# ShieldV1_2b.net
KiCad netlist of a schematic drawn in EasyEDA
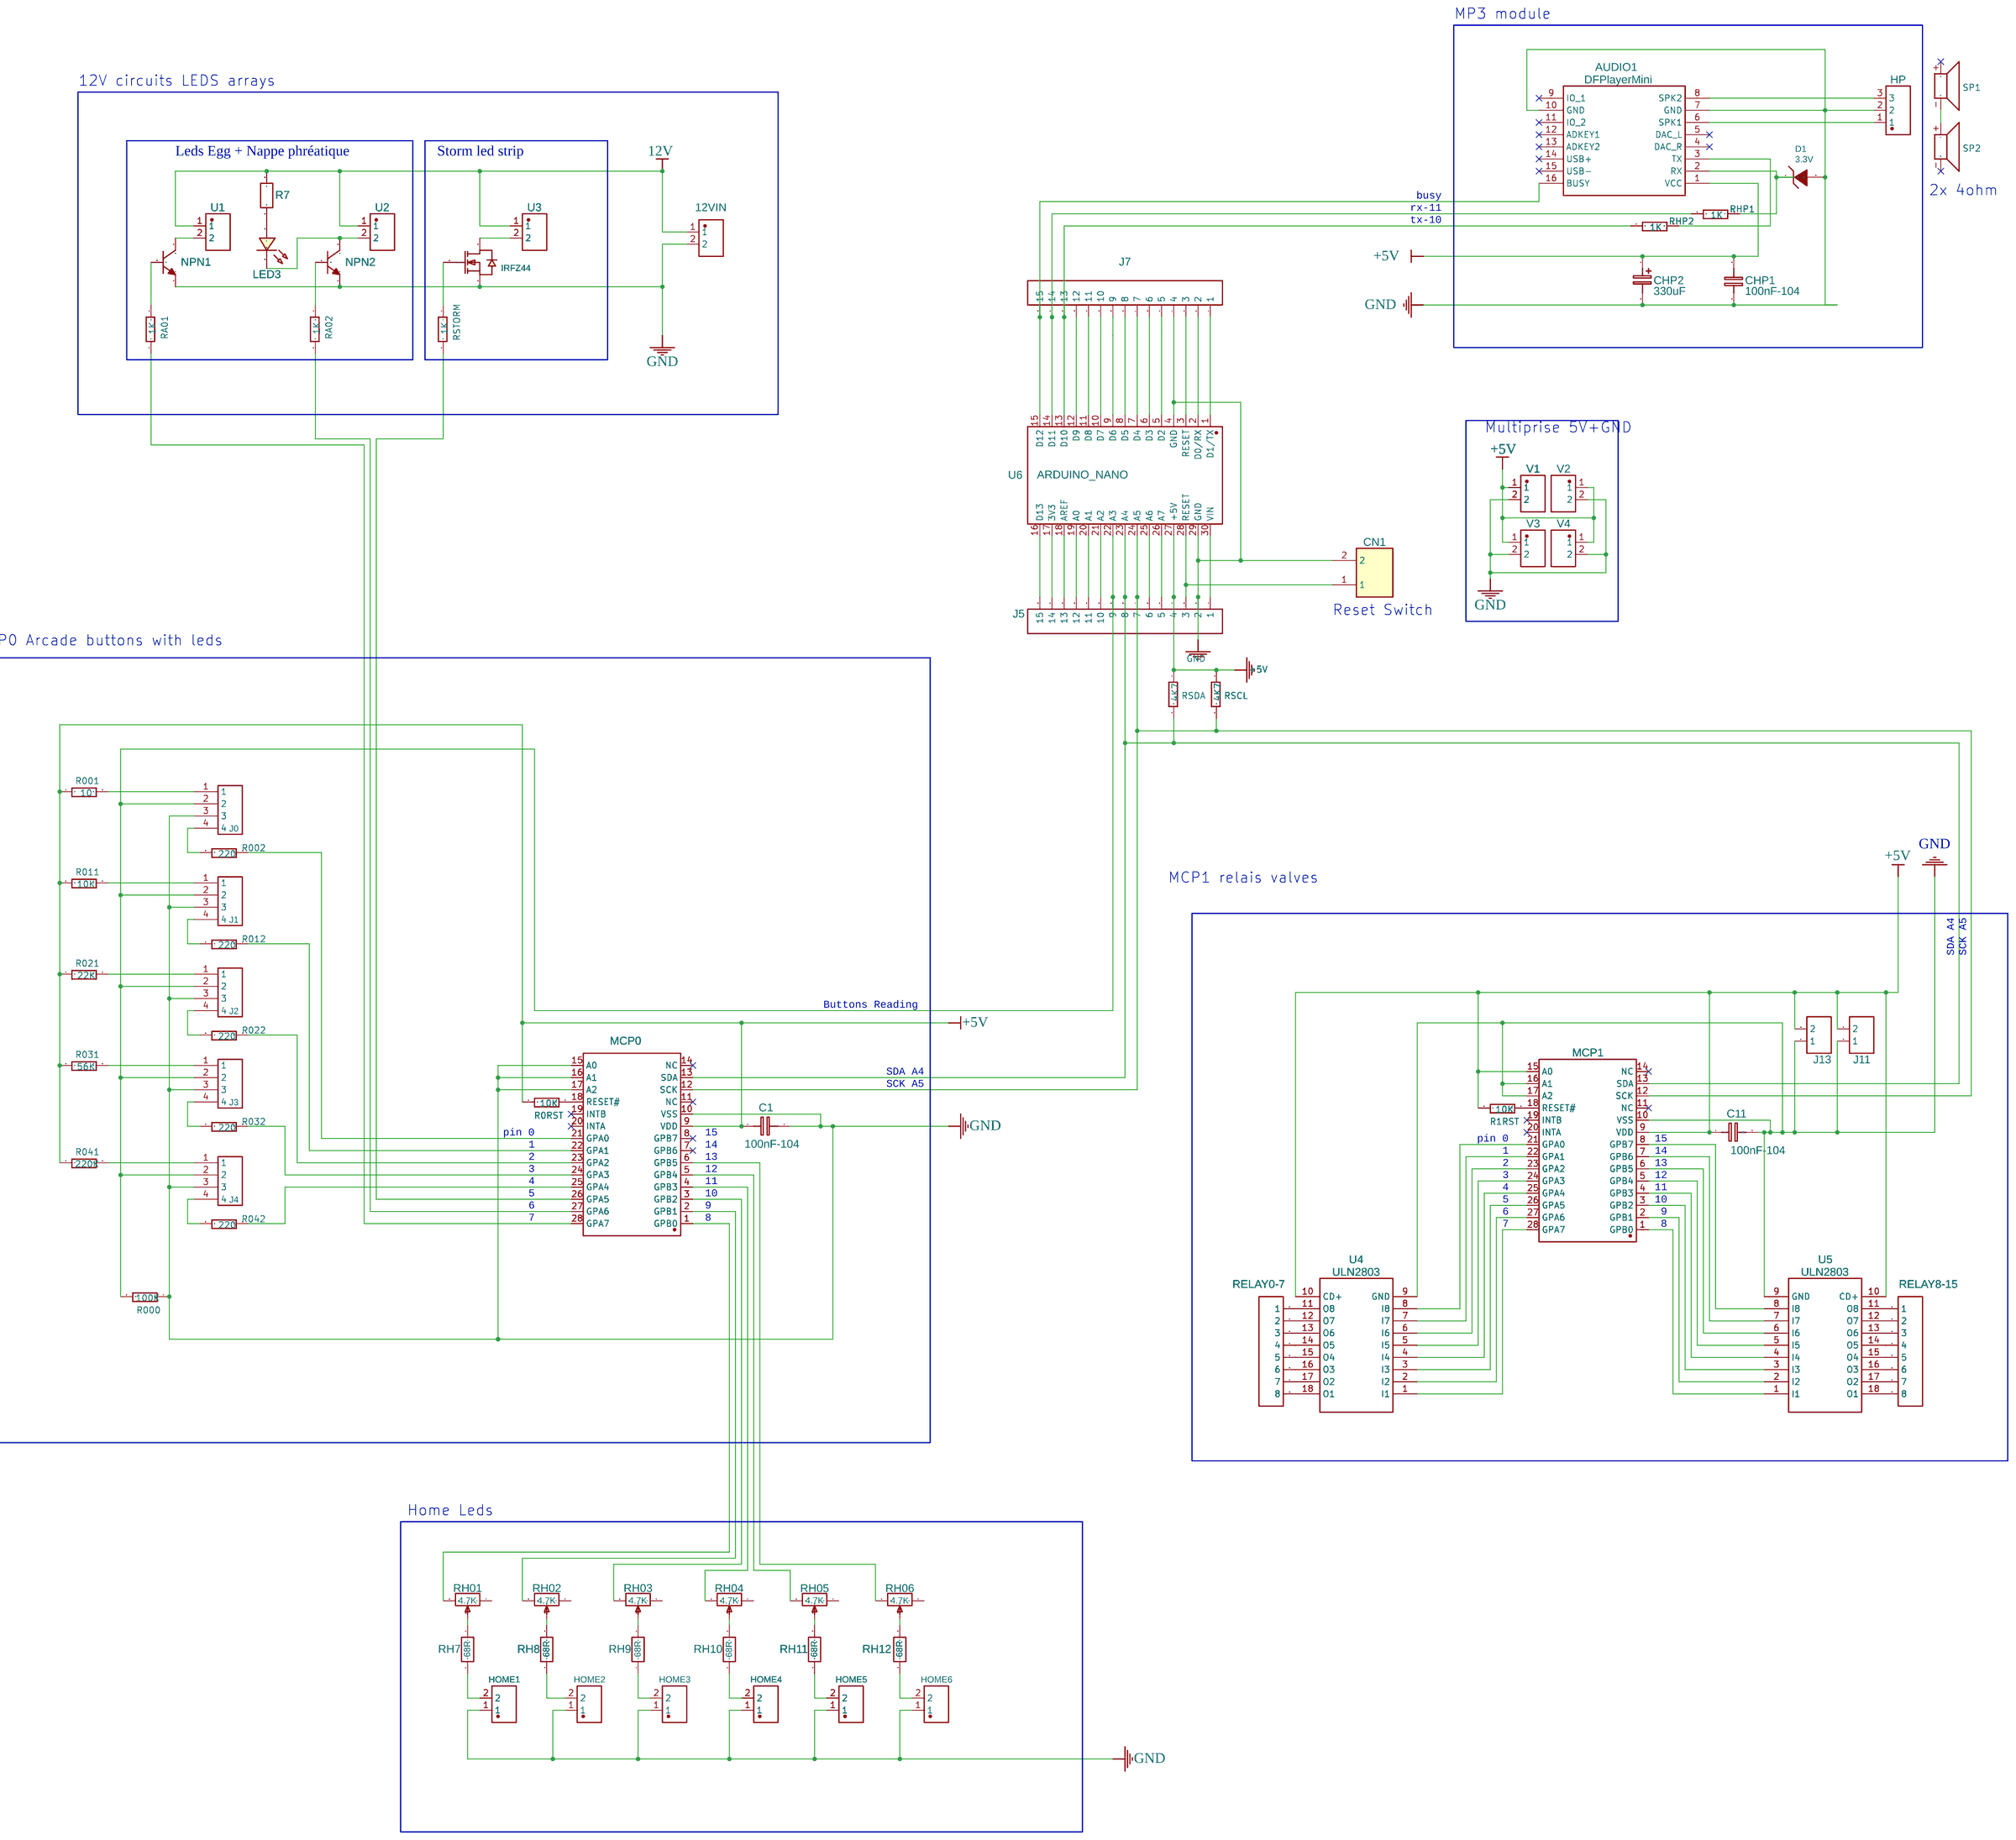
[diagram p0: Main board]
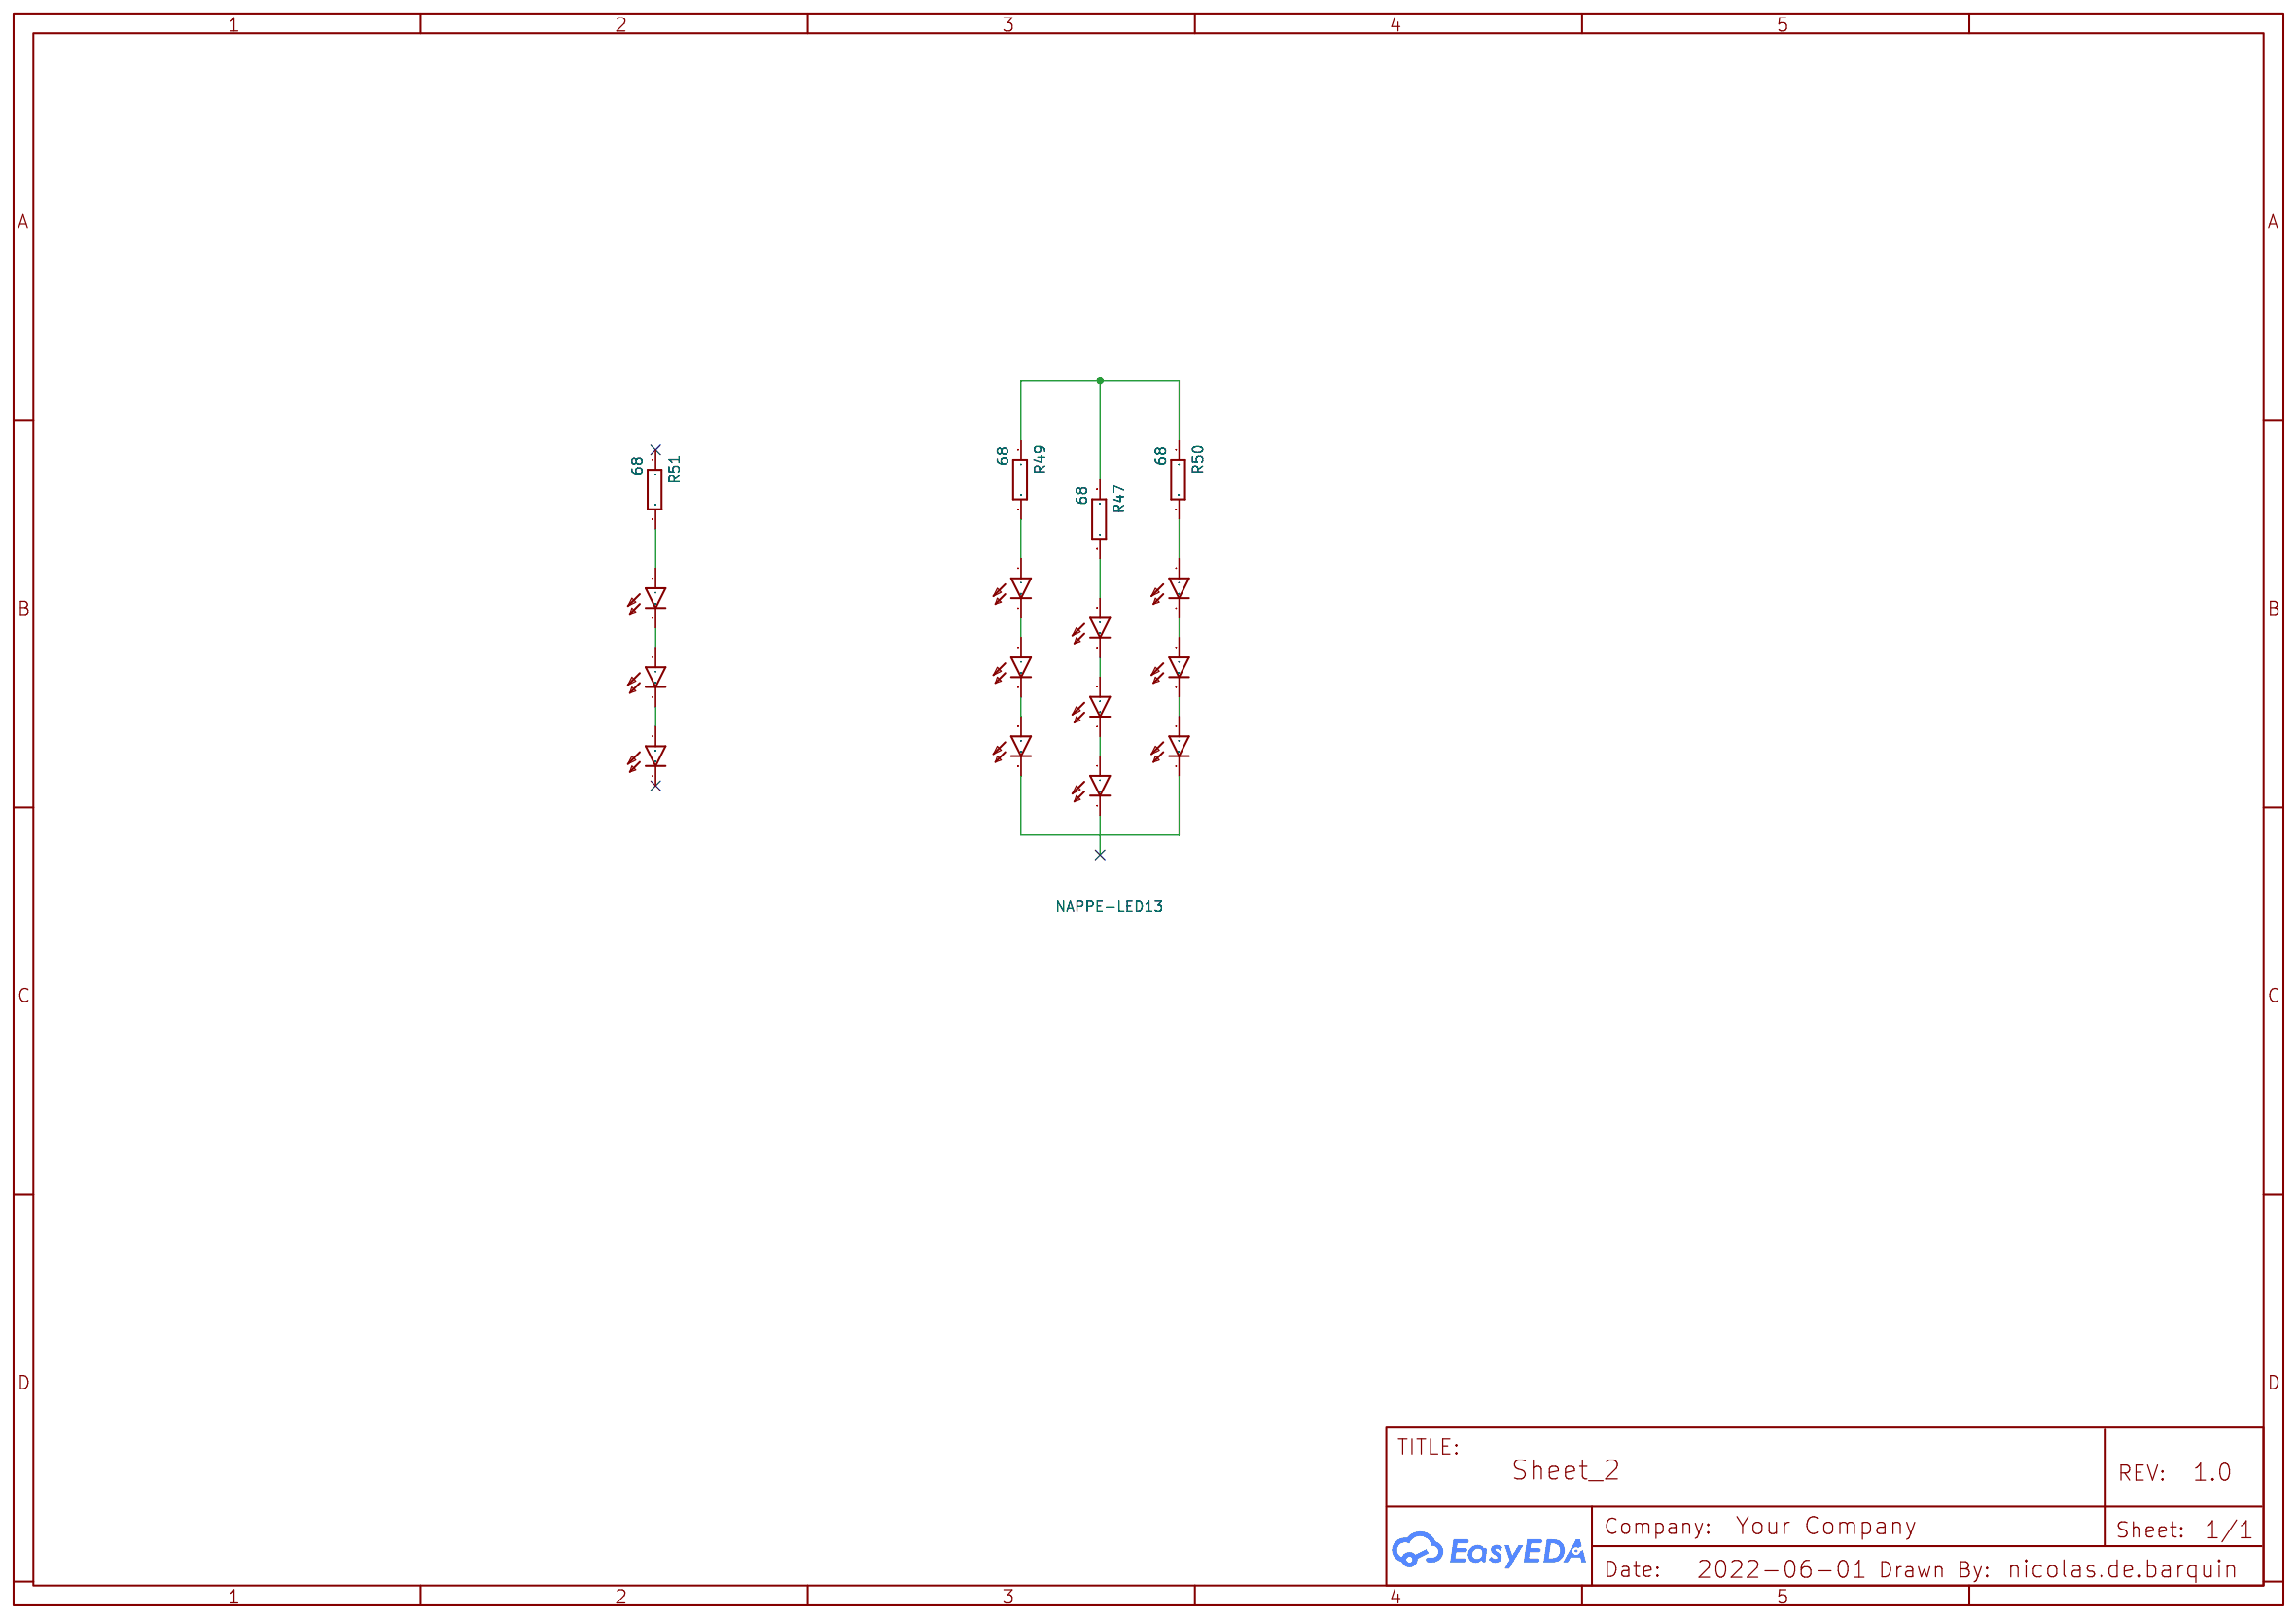
[diagram p1: leds]

(export (version "E")
  (design (tool "Eeschema 10.0.6"))
  (components
    (comp (ref "12VIN")
      (value "12V IN")
      (fields
        (field (name "BOM_Manufacturer Part") "KF301-5.0-2P")
        (field (name "BOM_Supplier Part") "C474881")
      )
      (libsource (lib "") (part "KF301-5.0-2P_1"))
    )
    (comp (ref "AUDIO1")
      (value "DFPlayerMini")
      (fields (field (name "BOM_Manufacturer Part") "DFPlayer mini"))
      (libsource (lib "") (part "DFPlayerMini"))
    )
    (comp (ref "C1") (value "100nF-104") (libsource (lib "") (part "C_RAD-0.1_EU_2")))
    (comp (ref "C11") (value "100nF-104") (libsource (lib "") (part "C_RAD-0.1_EU_1")))
    (comp (ref "CHP1") (value "100nF-104") (libsource (lib "") (part "C_RAD-0.1_EU")))
    (comp (ref "CHP2") (value "330uF") (libsource (lib "") (part "CE_TH_D6.3×F2.5_EU")))
    (comp (ref "CN1")
      (value "B2B-PH-K-S(LF)(SN)")
      (fields (field (name "BOM_Supplier Part") "C131337"))
      (libsource (lib "") (part "B2B-PH-K-S(LF)(SN)"))
    )
    (comp (ref "D1")
      (value "3.3V")
      (fields (field (name "BOM_Manufacturer Part") "1N5921BG") (field (name "BOM_Supplier Part") "C232466"))
      (libsource (lib "") (part "1N5921BG"))
    )
    (comp (ref "HOME1")
      (value "B2B-PH-KL")
      (fields (field (name "BOM_Supplier Part") "C2683610"))
      (libsource (lib "") (part "B2B-PH-KL"))
    )
    (comp (ref "HOME2")
      (value "B2B-PH-KL")
      (fields (field (name "BOM_Supplier Part") "C2683610"))
      (libsource (lib "") (part "B2B-PH-KL"))
    )
    (comp (ref "HOME3")
      (value "B2B-PH-KL")
      (fields (field (name "BOM_Supplier Part") "C2683610"))
      (libsource (lib "") (part "B2B-PH-KL"))
    )
    (comp (ref "HOME4")
      (value "B2B-PH-KL")
      (fields (field (name "BOM_Supplier Part") "C2683610"))
      (libsource (lib "") (part "B2B-PH-KL"))
    )
    (comp (ref "HOME5")
      (value "B2B-PH-KL")
      (fields (field (name "BOM_Supplier Part") "C2683610"))
      (libsource (lib "") (part "B2B-PH-KL"))
    )
    (comp (ref "HOME6")
      (value "B2B-PH-KL")
      (fields (field (name "BOM_Supplier Part") "C2683610"))
      (libsource (lib "") (part "B2B-PH-KL"))
    )
    (comp (ref "HP")
      (value "JL300-50003U01")
      (fields (field (name "BOM_Supplier Part") "C394552"))
      (libsource (lib "") (part "JL300-50003U01"))
    )
    (comp (ref "IRFZ44")
      (value "IRFZ44NPBF")
      (fields (field (name "BOM_Supplier Part") "C2586"))
      (libsource (lib "") (part "IRFZ44NPBF"))
    )
    (comp (ref "J0")
      (value "XHB-4A(White)/4needle")
      (fields (field (name "BOM_Supplier Part") "C61277"))
      (libsource (lib "") (part "XHB-4A(White)/4needle"))
    )
    (comp (ref "J1")
      (value "XHB-4A(White)/4needle")
      (fields (field (name "BOM_Supplier Part") "C61277"))
      (libsource (lib "") (part "XHB-4A(White)/4needle"))
    )
    (comp (ref "J2")
      (value "XHB-4A(White)/4needle")
      (fields (field (name "BOM_Supplier Part") "C61277"))
      (libsource (lib "") (part "XHB-4A(White)/4needle"))
    )
    (comp (ref "J3")
      (value "XHB-4A(White)/4needle")
      (fields (field (name "BOM_Supplier Part") "C61277"))
      (libsource (lib "") (part "XHB-4A(White)/4needle"))
    )
    (comp (ref "J4")
      (value "XHB-4A(White)/4needle")
      (fields (field (name "BOM_Supplier Part") "C61277"))
      (libsource (lib "") (part "XHB-4A(White)/4needle"))
    )
    (comp (ref "J5")
      (value "HDR-M-2.54_1x15")
      (fields (field (name "BOM_Supplier Part") "C124373"))
      (libsource (lib "") (part "HDR-M-2.54_1x15"))
    )
    (comp (ref "J7")
      (value "HDR-M-2.54_1x15")
      (fields (field (name "BOM_Supplier Part") "C124373"))
      (libsource (lib "") (part "HDR-M-2.54_1x15_1"))
    )
    (comp (ref "J11")
      (value "HDR-M-2.54_1x2")
      (fields (field (name "BOM_Supplier Part") "C124375"))
      (libsource (lib "") (part "HDR-M-2.54_1x2"))
    )
    (comp (ref "J13")
      (value "HDR-M-2.54_1x2")
      (fields (field (name "BOM_Supplier Part") "C124375"))
      (libsource (lib "") (part "HDR-M-2.54_1x2"))
    )
    (comp (ref "LED3")
      (value "LED-0805_R")
      (fields
        (field (name "BOM_Manufacturer Part") "17-21SURC/S530-A3/TR8")
        (field (name "BOM_Supplier Part") "C72037")
      )
      (libsource (lib "") (part "LED-0805_R"))
    )
    (comp (ref "MCP0")
      (value "MCP23017-E/SP")
      (fields (field (name "BOM_Supplier Part") "C647352"))
      (libsource (lib "") (part "MCP23017-E/SP"))
    )
    (comp (ref "MCP1")
      (value "MCP23017-E/SP")
      (fields (field (name "BOM_Supplier Part") "C647352"))
      (libsource (lib "") (part "MCP23017-E/SP"))
    )
    (comp (ref "NPN1")
      (value "2N4401_C15986")
      (fields (field (name "BOM_Manufacturer Part") "2N4401") (field (name "BOM_Supplier Part") "C15986"))
      (libsource (lib "") (part "2N4401_C15986"))
    )
    (comp (ref "NPN2")
      (value "2N4401_C15986")
      (fields (field (name "BOM_Manufacturer Part") "2N4401") (field (name "BOM_Supplier Part") "C15986"))
      (libsource (lib "") (part "2N4401_C15986"))
    )
    (comp (ref "R000") (value "100K") (libsource (lib "") (part "Unknown_875_-695")))
    (comp (ref "R0RST") (value "10K") (libsource (lib "") (part "Unknown_1205_-855")))
    (comp (ref "R001") (value "10") (libsource (lib "") (part "Unknown_825_-1110")))
    (comp (ref "R1RST") (value "10K") (libsource (lib "") (part "Unknown_1990_-850")))
    (comp (ref "R002") (value "220") (libsource (lib "") (part "Unknown_940_-1060")))
    (comp (ref "R7") (value "1k") (libsource (lib "") (part "R_0805_EU")))
    (comp (ref "R011") (value "10K") (libsource (lib "") (part "Unknown_825_-1035")))
    (comp (ref "R012") (value "220") (libsource (lib "") (part "Unknown_940_-985")))
    (comp (ref "R021") (value "22K") (libsource (lib "") (part "Unknown_825_-960")))
    (comp (ref "R022") (value "220") (libsource (lib "") (part "Unknown_940_-910")))
    (comp (ref "R031") (value "56K") (libsource (lib "") (part "Unknown_825_-885")))
    (comp (ref "R032") (value "220") (libsource (lib "") (part "Unknown_940_-835")))
    (comp (ref "R041") (value "220K") (libsource (lib "") (part "Unknown_825_-805")))
    (comp (ref "R042") (value "220") (libsource (lib "") (part "Unknown_940_-755")))
    (comp (ref "RA01") (value "1K") (libsource (lib "") (part "Unknown_880_-1490")))
    (comp (ref "RA02") (value "1K") (libsource (lib "") (part "Unknown_1015_-1490")))
    (comp (ref "RELAY0-7")
      (value "HDR-M-2.54_1x8")
      (fields (field (name "BOM_Supplier Part") "C190820"))
      (libsource (lib "") (part "HDR-M-2.54_1x8_1"))
    )
    (comp (ref "RELAY8-15")
      (value "HDR-M-2.54_1x8")
      (fields (field (name "BOM_Supplier Part") "C190820"))
      (libsource (lib "") (part "HDR-M-2.54_1x8"))
    )
    (comp (ref "RH01")
      (value "4.7K")
      (fields
        (field (name "BOM_Manufacturer Part") "GF063P1-B101")
        (field (name "BOM_Supplier Part") "C128075")
      )
      (libsource (lib "") (part "GF063P1-B101"))
    )
    (comp (ref "RH02")
      (value "4.7K")
      (fields
        (field (name "BOM_Manufacturer Part") "GF063P1-B101")
        (field (name "BOM_Supplier Part") "C128075")
      )
      (libsource (lib "") (part "GF063P1-B101"))
    )
    (comp (ref "RH03")
      (value "4.7K")
      (fields
        (field (name "BOM_Manufacturer Part") "GF063P1-B101")
        (field (name "BOM_Supplier Part") "C128075")
      )
      (libsource (lib "") (part "GF063P1-B101"))
    )
    (comp (ref "RH04")
      (value "4.7K")
      (fields
        (field (name "BOM_Manufacturer Part") "GF063P1-B101")
        (field (name "BOM_Supplier Part") "C128075")
      )
      (libsource (lib "") (part "GF063P1-B101"))
    )
    (comp (ref "RH05")
      (value "4.7K")
      (fields
        (field (name "BOM_Manufacturer Part") "GF063P1-B101")
        (field (name "BOM_Supplier Part") "C128075")
      )
      (libsource (lib "") (part "GF063P1-B101"))
    )
    (comp (ref "RH06")
      (value "4.7K")
      (fields
        (field (name "BOM_Manufacturer Part") "GF063P1-B101")
        (field (name "BOM_Supplier Part") "C128075")
      )
      (libsource (lib "") (part "GF063P1-B101"))
    )
    (comp (ref "RH7") (value "68R") (libsource (lib "") (part "R_0805_EU_1")))
    (comp (ref "RH8") (value "68R") (libsource (lib "") (part "R_0805_EU_1")))
    (comp (ref "RH9") (value "68R") (libsource (lib "") (part "R_0805_EU_1")))
    (comp (ref "RH10") (value "68R") (libsource (lib "") (part "R_0805_EU_1")))
    (comp (ref "RH11") (value "68R") (libsource (lib "") (part "R_0805_EU_1")))
    (comp (ref "RH12") (value "68R") (libsource (lib "") (part "R_0805_EU_1")))
    (comp (ref "RHP1") (value "1K") (libsource (lib "") (part "Unknown_2165_-1585")))
    (comp (ref "RHP2") (value "1K") (libsource (lib "") (part "Unknown_2115_-1575")))
    (comp (ref "RSCL") (value "4K7") (libsource (lib "") (part "Unknown_1755_-1190")))
    (comp (ref "RSDA") (value "4K7") (libsource (lib "") (part "Unknown_1720_-1190")))
    (comp (ref "RSTORM") (value "1K") (libsource (lib "") (part "Unknown_1120_-1490")))
    (comp (ref "SP1") (value "SMS-1308MS-2-R") (libsource (lib "") (part "Unknown_2350_-1690")))
    (comp (ref "SP2") (value "SMS-1308MS-2-R") (libsource (lib "") (part "Unknown_2350_-1640")))
    (comp (ref "U1")
      (value "KF301-5.0-2P")
      (fields (field (name "BOM_Supplier Part") "C474881"))
      (libsource (lib "") (part "KF301-5.0-2P"))
    )
    (comp (ref "U2")
      (value "KF301-5.0-2P")
      (fields (field (name "BOM_Supplier Part") "C474881"))
      (libsource (lib "") (part "KF301-5.0-2P"))
    )
    (comp (ref "U3")
      (value "KF301-5.0-2P")
      (fields (field (name "BOM_Supplier Part") "C474881"))
      (libsource (lib "") (part "KF301-5.0-2P"))
    )
    (comp (ref "U4")
      (value "ULN2803")
      (fields
        (field (name "BOM_Manufacturer Part") "ULN2803G-D18-T")
        (field (name "BOM_Supplier Part") "C75528")
      )
      (libsource (lib "") (part "ULN2803G-D18-T_1"))
    )
    (comp (ref "U5")
      (value "ULN2803")
      (fields
        (field (name "BOM_Manufacturer Part") "ULN2803G-D18-T")
        (field (name "BOM_Supplier Part") "C75528")
      )
      (libsource (lib "") (part "ULN2803G-D18-T"))
    )
    (comp (ref "U6")
      (value "ARDUINO_NANO")
      (fields (field (name "BOM_Supplier Part") "C9900017879"))
      (libsource (lib "") (part "ARDUINO_NANO"))
    )
    (comp (ref "V1")
      (value "12V IN")
      (fields
        (field (name "BOM_Manufacturer Part") "KF301-5.0-2P")
        (field (name "BOM_Supplier Part") "C474881")
      )
      (libsource (lib "") (part "KF301-5.0-2P_2"))
    )
    (comp (ref "V2")
      (value "12V IN")
      (fields
        (field (name "BOM_Manufacturer Part") "KF301-5.0-2P")
        (field (name "BOM_Supplier Part") "C474881")
      )
      (libsource (lib "") (part "KF301-5.0-2P_3"))
    )
    (comp (ref "V3")
      (value "12V IN")
      (fields
        (field (name "BOM_Manufacturer Part") "KF301-5.0-2P")
        (field (name "BOM_Supplier Part") "C474881")
      )
      (libsource (lib "") (part "KF301-5.0-2P_2"))
    )
    (comp (ref "V4")
      (value "12V IN")
      (fields
        (field (name "BOM_Manufacturer Part") "KF301-5.0-2P")
        (field (name "BOM_Supplier Part") "C474881")
      )
      (libsource (lib "") (part "KF301-5.0-2P_3"))
    )
    (comp (ref "NAPPE-LED1") (value "LED5MM") (libsource (lib "") (part "Unknown_550_-460")))
    (comp (ref "NAPPE-LED2") (value "LED5MM") (libsource (lib "") (part "Unknown_550_-500")))
    (comp (ref "NAPPE-LED3") (value "LED5MM") (libsource (lib "") (part "Unknown_510_-440")))
    (comp (ref "NAPPE-LED4") (value "LED5MM") (libsource (lib "") (part "Unknown_510_-480")))
    (comp (ref "NAPPE-LED5") (value "LED5MM") (libsource (lib "") (part "Unknown_510_-520")))
    (comp (ref "NAPPE-LED6") (value "LED5MM") (libsource (lib "") (part "Unknown_590_-440")))
    (comp (ref "NAPPE-LED7") (value "LED5MM") (libsource (lib "") (part "Unknown_590_-480")))
    (comp (ref "NAPPE-LED8") (value "LED5MM") (libsource (lib "") (part "Unknown_590_-520")))
    (comp (ref "NAPPE-LED9") (value "LED5MM") (libsource (lib "") (part "Unknown_325_-435")))
    (comp (ref "NAPPE-LED10") (value "LED5MM") (libsource (lib "") (part "Unknown_325_-475")))
    (comp (ref "NAPPE-LED11") (value "LED5MM") (libsource (lib "") (part "Unknown_325_-515")))
    (comp (ref "NAPPE-LED13") (value "LED5MM") (libsource (lib "") (part "Unknown_550_-420")))
    (comp (ref "R47") (value "68") (libsource (lib "") (part "Unknown_550_-550")))
    (comp (ref "R49") (value "68") (libsource (lib "") (part "Unknown_510_-570")))
    (comp (ref "R50") (value "68") (libsource (lib "") (part "Unknown_590_-570")))
    (comp (ref "R51") (value "68") (libsource (lib "") (part "Unknown_325_-565")))
  )
  (nets
    (net (code "1") (name "+5V") (class "Default")
      (node (ref "AUDIO1") (pin "1") (pinfunction "VCC_1") (pintype "unspecified"))
      (node (ref "C1") (pin "1") (pinfunction "1_1") (pintype "unspecified"))
      (node (ref "C11") (pin "1") (pinfunction "1_1") (pintype "unspecified"))
      (node (ref "CHP1") (pin "2") (pinfunction "2_2") (pintype "unspecified"))
      (node (ref "CHP2") (pin "1") (pinfunction "1_1") (pintype "unspecified"))
      (node (ref "J11") (pin "2") (pinfunction "2_2") (pintype "unspecified"))
      (node (ref "J13") (pin "2") (pinfunction "2_2") (pintype "unspecified"))
      (node (ref "J5") (pin "4") (pinfunction "4_4") (pintype "unspecified"))
      (node (ref "MCP0") (pin "9") (pinfunction "VDD_9") (pintype "unspecified"))
      (node (ref "MCP1") (pin "15") (pinfunction "A0_15") (pintype "unspecified"))
      (node (ref "MCP1") (pin "9") (pinfunction "VDD_9") (pintype "unspecified"))
      (node (ref "R001") (pin "2") (pinfunction "2_2") (pintype "bidirectional"))
      (node (ref "R011") (pin "2") (pinfunction "2_2") (pintype "bidirectional"))
      (node (ref "R021") (pin "2") (pinfunction "2_2") (pintype "bidirectional"))
      (node (ref "R031") (pin "2") (pinfunction "2_2") (pintype "bidirectional"))
      (node (ref "R041") (pin "2") (pinfunction "2_2") (pintype "bidirectional"))
      (node (ref "R0RST") (pin "2") (pinfunction "2_2") (pintype "bidirectional"))
      (node (ref "R1RST") (pin "2") (pinfunction "2_2") (pintype "bidirectional"))
      (node (ref "RSCL") (pin "1") (pinfunction "1_1") (pintype "bidirectional"))
      (node (ref "RSDA") (pin "1") (pinfunction "1_1") (pintype "bidirectional"))
      (node (ref "U4") (pin "10") (pinfunction "CD+_10") (pintype "unspecified"))
      (node (ref "U5") (pin "10") (pinfunction "CD+_10") (pintype "unspecified"))
      (node (ref "U6") (pin "27") (pinfunction "+5V_27") (pintype "unspecified"))
      (node (ref "V1") (pin "1") (pinfunction "1_1") (pintype "unspecified"))
      (node (ref "V2") (pin "1") (pinfunction "1_1") (pintype "unspecified"))
      (node (ref "V3") (pin "1") (pinfunction "1_1") (pintype "unspecified"))
      (node (ref "V4") (pin "1") (pinfunction "1_1") (pintype "unspecified"))
    )
    (net (code "2") (name "12V") (class "Default")
      (node (ref "12VIN") (pin "1") (pinfunction "1_1") (pintype "unspecified"))
      (node (ref "R7") (pin "2") (pinfunction "2_2") (pintype "unspecified"))
      (node (ref "U1") (pin "1") (pinfunction "1_1") (pintype "unspecified"))
      (node (ref "U2") (pin "1") (pinfunction "1_1") (pintype "unspecified"))
      (node (ref "U3") (pin "1") (pinfunction "1_1") (pintype "unspecified"))
    )
    (net (code "3") (name "GND") (class "Default")
      (node (ref "12VIN") (pin "2") (pinfunction "2_2") (pintype "unspecified"))
      (node (ref "AUDIO1") (pin "10") (pinfunction "GND_10") (pintype "unspecified"))
      (node (ref "AUDIO1") (pin "7") (pinfunction "GND_7") (pintype "unspecified"))
      (node (ref "C1") (pin "2") (pinfunction "2_2") (pintype "unspecified"))
      (node (ref "C11") (pin "2") (pinfunction "2_2") (pintype "unspecified"))
      (node (ref "CHP1") (pin "1") (pinfunction "1_1") (pintype "unspecified"))
      (node (ref "CHP2") (pin "2") (pinfunction "2_2") (pintype "unspecified"))
      (node (ref "CN1") (pin "2") (pinfunction "2_2") (pintype "input"))
      (node (ref "D1") (pin "2") (pinfunction "A_2") (pintype "unspecified"))
      (node (ref "HOME1") (pin "1") (pinfunction "1_1") (pintype "unspecified"))
      (node (ref "HOME2") (pin "1") (pinfunction "1_1") (pintype "unspecified"))
      (node (ref "HOME3") (pin "1") (pinfunction "1_1") (pintype "unspecified"))
      (node (ref "HOME4") (pin "1") (pinfunction "1_1") (pintype "unspecified"))
      (node (ref "HOME5") (pin "1") (pinfunction "1_1") (pintype "unspecified"))
      (node (ref "HOME6") (pin "1") (pinfunction "1_1") (pintype "unspecified"))
      (node (ref "HP") (pin "2") (pinfunction "2_2") (pintype "unspecified"))
      (node (ref "IRFZ44") (pin "3") (pinfunction "S_3") (pintype "unspecified"))
      (node (ref "J0") (pin "3") (pinfunction "3_3") (pintype "unspecified"))
      (node (ref "J1") (pin "3") (pinfunction "3_3") (pintype "unspecified"))
      (node (ref "J11") (pin "1") (pinfunction "1_1") (pintype "unspecified"))
      (node (ref "J13") (pin "1") (pinfunction "1_1") (pintype "unspecified"))
      (node (ref "J2") (pin "3") (pinfunction "3_3") (pintype "unspecified"))
      (node (ref "J3") (pin "3") (pinfunction "3_3") (pintype "unspecified"))
      (node (ref "J4") (pin "3") (pinfunction "3_3") (pintype "unspecified"))
      (node (ref "J5") (pin "2") (pinfunction "2_2") (pintype "unspecified"))
      (node (ref "J7") (pin "4") (pinfunction "4_4") (pintype "unspecified"))
      (node (ref "MCP0") (pin "10") (pinfunction "VSS_10") (pintype "unspecified"))
      (node (ref "MCP0") (pin "15") (pinfunction "A0_15") (pintype "unspecified"))
      (node (ref "MCP0") (pin "16") (pinfunction "A1_16") (pintype "unspecified"))
      (node (ref "MCP0") (pin "17") (pinfunction "A2_17") (pintype "unspecified"))
      (node (ref "MCP1") (pin "10") (pinfunction "VSS_10") (pintype "unspecified"))
      (node (ref "MCP1") (pin "16") (pinfunction "A1_16") (pintype "unspecified"))
      (node (ref "MCP1") (pin "17") (pinfunction "A2_17") (pintype "unspecified"))
      (node (ref "NPN1") (pin "1") (pinfunction "E_1") (pintype "unspecified"))
      (node (ref "NPN2") (pin "1") (pinfunction "E_1") (pintype "unspecified"))
      (node (ref "R000") (pin "1") (pinfunction "1_1") (pintype "bidirectional"))
      (node (ref "U4") (pin "9") (pinfunction "GND_9") (pintype "passive"))
      (node (ref "U5") (pin "9") (pinfunction "GND_9") (pintype "passive"))
      (node (ref "U6") (pin "29") (pinfunction "GND_29") (pintype "unspecified"))
      (node (ref "U6") (pin "4") (pinfunction "GND_4") (pintype "unspecified"))
      (node (ref "V1") (pin "2") (pinfunction "2_2") (pintype "unspecified"))
      (node (ref "V2") (pin "2") (pinfunction "2_2") (pintype "unspecified"))
      (node (ref "V3") (pin "2") (pinfunction "2_2") (pintype "unspecified"))
      (node (ref "V4") (pin "2") (pinfunction "2_2") (pintype "unspecified"))
    )
    (net (code "4") (name "Net-(AUDIO1-BUSY)") (class "Default")
      (node (ref "AUDIO1") (pin "16") (pinfunction "BUSY_16") (pintype "unspecified"))
      (node (ref "J7") (pin "15") (pinfunction "15_15") (pintype "unspecified"))
      (node (ref "U6") (pin "15") (pinfunction "D12_15") (pintype "unspecified"))
    )
    (net (code "5") (name "Net-(AUDIO1-RX)") (class "Default")
      (node (ref "AUDIO1") (pin "2") (pinfunction "RX_2") (pintype "unspecified"))
      (node (ref "D1") (pin "1") (pinfunction "C_1") (pintype "unspecified"))
      (node (ref "RHP1") (pin "1") (pinfunction "1_1") (pintype "bidirectional"))
    )
    (net (code "6") (name "Net-(AUDIO1-SPK1)") (class "Default")
      (node (ref "AUDIO1") (pin "6") (pinfunction "SPK1_6") (pintype "unspecified"))
      (node (ref "HP") (pin "1") (pinfunction "1_1") (pintype "unspecified"))
    )
    (net (code "7") (name "Net-(AUDIO1-SPK2)") (class "Default")
      (node (ref "AUDIO1") (pin "8") (pinfunction "SPK2_8") (pintype "unspecified"))
      (node (ref "HP") (pin "3") (pinfunction "3_3") (pintype "unspecified"))
    )
    (net (code "8") (name "Net-(AUDIO1-TX)") (class "Default")
      (node (ref "AUDIO1") (pin "3") (pinfunction "TX_3") (pintype "unspecified"))
      (node (ref "RHP2") (pin "2") (pinfunction "2_2") (pintype "bidirectional"))
    )
    (net (code "9") (name "Net-(CN1-Pad1)") (class "Default")
      (node (ref "CN1") (pin "1") (pinfunction "1_1") (pintype "input"))
      (node (ref "J5") (pin "3") (pinfunction "3_3") (pintype "unspecified"))
      (node (ref "U6") (pin "28") (pinfunction "RESET_28") (pintype "unspecified"))
    )
    (net (code "10") (name "Net-(HOME1-Pad2)") (class "Default")
      (node (ref "HOME1") (pin "2") (pinfunction "2_2") (pintype "unspecified"))
      (node (ref "RH7") (pin "1") (pinfunction "1_1") (pintype "unspecified"))
    )
    (net (code "11") (name "Net-(HOME2-Pad2)") (class "Default")
      (node (ref "HOME2") (pin "2") (pinfunction "2_2") (pintype "unspecified"))
      (node (ref "RH8") (pin "1") (pinfunction "1_1") (pintype "unspecified"))
    )
    (net (code "12") (name "Net-(HOME3-Pad2)") (class "Default")
      (node (ref "HOME3") (pin "2") (pinfunction "2_2") (pintype "unspecified"))
      (node (ref "RH9") (pin "1") (pinfunction "1_1") (pintype "unspecified"))
    )
    (net (code "13") (name "Net-(HOME4-Pad2)") (class "Default")
      (node (ref "HOME4") (pin "2") (pinfunction "2_2") (pintype "unspecified"))
      (node (ref "RH10") (pin "1") (pinfunction "1_1") (pintype "unspecified"))
    )
    (net (code "14") (name "Net-(HOME5-Pad2)") (class "Default")
      (node (ref "HOME5") (pin "2") (pinfunction "2_2") (pintype "unspecified"))
      (node (ref "RH11") (pin "1") (pinfunction "1_1") (pintype "unspecified"))
    )
    (net (code "15") (name "Net-(HOME6-Pad2)") (class "Default")
      (node (ref "HOME6") (pin "2") (pinfunction "2_2") (pintype "unspecified"))
      (node (ref "RH12") (pin "1") (pinfunction "1_1") (pintype "unspecified"))
    )
    (net (code "16") (name "Net-(IRFZ44-D)") (class "Default")
      (node (ref "IRFZ44") (pin "2") (pinfunction "D_2") (pintype "unspecified"))
      (node (ref "U3") (pin "2") (pinfunction "2_2") (pintype "unspecified"))
    )
    (net (code "17") (name "Net-(IRFZ44-G)") (class "Default")
      (node (ref "IRFZ44") (pin "1") (pinfunction "G_1") (pintype "unspecified"))
      (node (ref "RSTORM") (pin "1") (pinfunction "1_1") (pintype "bidirectional"))
    )
    (net (code "18") (name "Net-(J0-Pad1)") (class "Default")
      (node (ref "J0") (pin "1") (pinfunction "1_1") (pintype "unspecified"))
      (node (ref "R001") (pin "1") (pinfunction "1_1") (pintype "bidirectional"))
    )
    (net (code "19") (name "Net-(J0-Pad4)") (class "Default")
      (node (ref "J0") (pin "4") (pinfunction "4_4") (pintype "unspecified"))
      (node (ref "R002") (pin "2") (pinfunction "2_2") (pintype "bidirectional"))
    )
    (net (code "20") (name "Net-(J1-Pad1)") (class "Default")
      (node (ref "J1") (pin "1") (pinfunction "1_1") (pintype "unspecified"))
      (node (ref "R011") (pin "1") (pinfunction "1_1") (pintype "bidirectional"))
    )
    (net (code "21") (name "Net-(J1-Pad4)") (class "Default")
      (node (ref "J1") (pin "4") (pinfunction "4_4") (pintype "unspecified"))
      (node (ref "R012") (pin "2") (pinfunction "2_2") (pintype "bidirectional"))
    )
    (net (code "22") (name "Net-(J2-Pad1)") (class "Default")
      (node (ref "J2") (pin "1") (pinfunction "1_1") (pintype "unspecified"))
      (node (ref "R021") (pin "1") (pinfunction "1_1") (pintype "bidirectional"))
    )
    (net (code "23") (name "Net-(J2-Pad4)") (class "Default")
      (node (ref "J2") (pin "4") (pinfunction "4_4") (pintype "unspecified"))
      (node (ref "R022") (pin "2") (pinfunction "2_2") (pintype "bidirectional"))
    )
    (net (code "24") (name "Net-(J3-Pad1)") (class "Default")
      (node (ref "J3") (pin "1") (pinfunction "1_1") (pintype "unspecified"))
      (node (ref "R031") (pin "1") (pinfunction "1_1") (pintype "bidirectional"))
    )
    (net (code "25") (name "Net-(J3-Pad4)") (class "Default")
      (node (ref "J3") (pin "4") (pinfunction "4_4") (pintype "unspecified"))
      (node (ref "R032") (pin "2") (pinfunction "2_2") (pintype "bidirectional"))
    )
    (net (code "26") (name "Net-(J4-Pad1)") (class "Default")
      (node (ref "J4") (pin "1") (pinfunction "1_1") (pintype "unspecified"))
      (node (ref "R041") (pin "1") (pinfunction "1_1") (pintype "bidirectional"))
    )
    (net (code "27") (name "Net-(J4-Pad4)") (class "Default")
      (node (ref "J4") (pin "4") (pinfunction "4_4") (pintype "unspecified"))
      (node (ref "R042") (pin "2") (pinfunction "2_2") (pintype "bidirectional"))
    )
    (net (code "28") (name "Net-(J7-Pad3)") (class "Default")
      (node (ref "J7") (pin "3") (pinfunction "3_3") (pintype "unspecified"))
      (node (ref "U6") (pin "3") (pinfunction "RESET_3") (pintype "unspecified"))
    )
    (net (code "29") (name "Net-(LED3-Pad1)") (class "Default")
      (node (ref "LED3") (pin "1") (pinfunction "1_1") (pintype "unspecified"))
      (node (ref "R7") (pin "1") (pinfunction "1_1") (pintype "unspecified"))
    )
    (net (code "30") (name "Net-(MCP0-GPA0)") (class "Default")
      (node (ref "MCP0") (pin "21") (pinfunction "GPA0_21") (pintype "unspecified"))
      (node (ref "R002") (pin "1") (pinfunction "1_1") (pintype "bidirectional"))
    )
    (net (code "31") (name "Net-(MCP0-GPA1)") (class "Default")
      (node (ref "MCP0") (pin "22") (pinfunction "GPA1_22") (pintype "unspecified"))
      (node (ref "R012") (pin "1") (pinfunction "1_1") (pintype "bidirectional"))
    )
    (net (code "32") (name "Net-(MCP0-GPA2)") (class "Default")
      (node (ref "MCP0") (pin "23") (pinfunction "GPA2_23") (pintype "unspecified"))
      (node (ref "R022") (pin "1") (pinfunction "1_1") (pintype "bidirectional"))
    )
    (net (code "33") (name "Net-(MCP0-GPA3)") (class "Default")
      (node (ref "MCP0") (pin "24") (pinfunction "GPA3_24") (pintype "unspecified"))
      (node (ref "R032") (pin "1") (pinfunction "1_1") (pintype "bidirectional"))
    )
    (net (code "34") (name "Net-(MCP0-GPA4)") (class "Default")
      (node (ref "MCP0") (pin "25") (pinfunction "GPA4_25") (pintype "unspecified"))
      (node (ref "R042") (pin "1") (pinfunction "1_1") (pintype "bidirectional"))
    )
    (net (code "35") (name "Net-(MCP0-GPA5)") (class "Default")
      (node (ref "MCP0") (pin "26") (pinfunction "GPA5_26") (pintype "unspecified"))
      (node (ref "RSTORM") (pin "2") (pinfunction "2_2") (pintype "bidirectional"))
    )
    (net (code "36") (name "Net-(MCP0-GPA6)") (class "Default")
      (node (ref "MCP0") (pin "27") (pinfunction "GPA6_27") (pintype "unspecified"))
      (node (ref "RA02") (pin "2") (pinfunction "2_2") (pintype "bidirectional"))
    )
    (net (code "37") (name "Net-(MCP0-GPA7)") (class "Default")
      (node (ref "MCP0") (pin "28") (pinfunction "GPA7_28") (pintype "unspecified"))
      (node (ref "RA01") (pin "2") (pinfunction "2_2") (pintype "bidirectional"))
    )
    (net (code "38") (name "Net-(MCP0-GPB0)") (class "Default")
      (node (ref "MCP0") (pin "1") (pinfunction "GPB0_1") (pintype "unspecified"))
      (node (ref "RH01") (pin "3") (pinfunction "3_3") (pintype "input"))
    )
    (net (code "39") (name "Net-(MCP0-GPB1)") (class "Default")
      (node (ref "MCP0") (pin "2") (pinfunction "GPB1_2") (pintype "unspecified"))
      (node (ref "RH02") (pin "3") (pinfunction "3_3") (pintype "input"))
    )
    (net (code "40") (name "Net-(MCP0-GPB2)") (class "Default")
      (node (ref "MCP0") (pin "3") (pinfunction "GPB2_3") (pintype "unspecified"))
      (node (ref "RH03") (pin "3") (pinfunction "3_3") (pintype "input"))
    )
    (net (code "41") (name "Net-(MCP0-GPB3)") (class "Default")
      (node (ref "MCP0") (pin "4") (pinfunction "GPB3_4") (pintype "unspecified"))
      (node (ref "RH04") (pin "3") (pinfunction "3_3") (pintype "input"))
    )
    (net (code "42") (name "Net-(MCP0-GPB4)") (class "Default")
      (node (ref "MCP0") (pin "5") (pinfunction "GPB4_5") (pintype "unspecified"))
      (node (ref "RH05") (pin "3") (pinfunction "3_3") (pintype "input"))
    )
    (net (code "43") (name "Net-(MCP0-GPB5)") (class "Default")
      (node (ref "MCP0") (pin "6") (pinfunction "GPB5_6") (pintype "unspecified"))
      (node (ref "RH06") (pin "3") (pinfunction "3_3") (pintype "input"))
    )
    (net (code "44") (name "Net-(MCP0-RESET#)") (class "Default")
      (node (ref "MCP0") (pin "18") (pinfunction "RESET#_18") (pintype "unspecified"))
      (node (ref "R0RST") (pin "1") (pinfunction "1_1") (pintype "bidirectional"))
    )
    (net (code "45") (name "Net-(MCP0-SCK)") (class "Default")
      (node (ref "J5") (pin "7") (pinfunction "7_7") (pintype "unspecified"))
      (node (ref "MCP0") (pin "12") (pinfunction "SCK_12") (pintype "unspecified"))
      (node (ref "MCP1") (pin "12") (pinfunction "SCK_12") (pintype "unspecified"))
      (node (ref "RSCL") (pin "2") (pinfunction "2_2") (pintype "bidirectional"))
      (node (ref "U6") (pin "24") (pinfunction "A5_24") (pintype "unspecified"))
    )
    (net (code "46") (name "Net-(MCP0-SDA)") (class "Default")
      (node (ref "J5") (pin "8") (pinfunction "8_8") (pintype "unspecified"))
      (node (ref "MCP0") (pin "13") (pinfunction "SDA_13") (pintype "unspecified"))
      (node (ref "MCP1") (pin "13") (pinfunction "SDA_13") (pintype "unspecified"))
      (node (ref "RSDA") (pin "2") (pinfunction "2_2") (pintype "bidirectional"))
      (node (ref "U6") (pin "23") (pinfunction "A4_23") (pintype "unspecified"))
    )
    (net (code "47") (name "Net-(MCP1-GPA0)") (class "Default")
      (node (ref "MCP1") (pin "21") (pinfunction "GPA0_21") (pintype "unspecified"))
      (node (ref "U4") (pin "8") (pinfunction "I8_8") (pintype "input"))
    )
    (net (code "48") (name "Net-(MCP1-GPA1)") (class "Default")
      (node (ref "MCP1") (pin "22") (pinfunction "GPA1_22") (pintype "unspecified"))
      (node (ref "U4") (pin "7") (pinfunction "I7_7") (pintype "input"))
    )
    (net (code "49") (name "Net-(MCP1-GPA2)") (class "Default")
      (node (ref "MCP1") (pin "23") (pinfunction "GPA2_23") (pintype "unspecified"))
      (node (ref "U4") (pin "6") (pinfunction "I6_6") (pintype "input"))
    )
    (net (code "50") (name "Net-(MCP1-GPA3)") (class "Default")
      (node (ref "MCP1") (pin "24") (pinfunction "GPA3_24") (pintype "unspecified"))
      (node (ref "U4") (pin "5") (pinfunction "I5_5") (pintype "input"))
    )
    (net (code "51") (name "Net-(MCP1-GPA4)") (class "Default")
      (node (ref "MCP1") (pin "25") (pinfunction "GPA4_25") (pintype "unspecified"))
      (node (ref "U4") (pin "4") (pinfunction "I4_4") (pintype "input"))
    )
    (net (code "52") (name "Net-(MCP1-GPA5)") (class "Default")
      (node (ref "MCP1") (pin "26") (pinfunction "GPA5_26") (pintype "unspecified"))
      (node (ref "U4") (pin "3") (pinfunction "I3_3") (pintype "input"))
    )
    (net (code "53") (name "Net-(MCP1-GPA6)") (class "Default")
      (node (ref "MCP1") (pin "27") (pinfunction "GPA6_27") (pintype "unspecified"))
      (node (ref "U4") (pin "2") (pinfunction "I2_2") (pintype "input"))
    )
    (net (code "54") (name "Net-(MCP1-GPA7)") (class "Default")
      (node (ref "MCP1") (pin "28") (pinfunction "GPA7_28") (pintype "unspecified"))
      (node (ref "U4") (pin "1") (pinfunction "I1_1") (pintype "input"))
    )
    (net (code "55") (name "Net-(MCP1-GPB0)") (class "Default")
      (node (ref "MCP1") (pin "1") (pinfunction "GPB0_1") (pintype "unspecified"))
      (node (ref "U5") (pin "1") (pinfunction "I1_1") (pintype "input"))
    )
    (net (code "56") (name "Net-(MCP1-GPB1)") (class "Default")
      (node (ref "MCP1") (pin "2") (pinfunction "GPB1_2") (pintype "unspecified"))
      (node (ref "U5") (pin "2") (pinfunction "I2_2") (pintype "input"))
    )
    (net (code "57") (name "Net-(MCP1-GPB2)") (class "Default")
      (node (ref "MCP1") (pin "3") (pinfunction "GPB2_3") (pintype "unspecified"))
      (node (ref "U5") (pin "3") (pinfunction "I3_3") (pintype "input"))
    )
    (net (code "58") (name "Net-(MCP1-GPB3)") (class "Default")
      (node (ref "MCP1") (pin "4") (pinfunction "GPB3_4") (pintype "unspecified"))
      (node (ref "U5") (pin "4") (pinfunction "I4_4") (pintype "input"))
    )
    (net (code "59") (name "Net-(MCP1-GPB4)") (class "Default")
      (node (ref "MCP1") (pin "5") (pinfunction "GPB4_5") (pintype "unspecified"))
      (node (ref "U5") (pin "5") (pinfunction "I5_5") (pintype "input"))
    )
    (net (code "60") (name "Net-(MCP1-GPB5)") (class "Default")
      (node (ref "MCP1") (pin "6") (pinfunction "GPB5_6") (pintype "unspecified"))
      (node (ref "U5") (pin "6") (pinfunction "I6_6") (pintype "input"))
    )
    (net (code "61") (name "Net-(MCP1-GPB6)") (class "Default")
      (node (ref "MCP1") (pin "7") (pinfunction "GPB6_7") (pintype "unspecified"))
      (node (ref "U5") (pin "7") (pinfunction "I7_7") (pintype "input"))
    )
    (net (code "62") (name "Net-(MCP1-GPB7)") (class "Default")
      (node (ref "MCP1") (pin "8") (pinfunction "GPB7_8") (pintype "unspecified"))
      (node (ref "U5") (pin "8") (pinfunction "I8_8") (pintype "input"))
    )
    (net (code "63") (name "Net-(MCP1-RESET#)") (class "Default")
      (node (ref "MCP1") (pin "18") (pinfunction "RESET#_18") (pintype "unspecified"))
      (node (ref "R1RST") (pin "1") (pinfunction "1_1") (pintype "bidirectional"))
    )
    (net (code "64") (name "Net-(NAPPE-LED1-C)") (class "Default")
      (node (ref "NAPPE-LED1") (pin "K") (pinfunction "C_K") (pintype "bidirectional"))
      (node (ref "NAPPE-LED13") (pin "A") (pinfunction "A_A") (pintype "bidirectional"))
    )
    (net (code "65") (name "Net-(NAPPE-LED2-C)") (class "Default")
      (node (ref "NAPPE-LED1") (pin "A") (pinfunction "A_A") (pintype "bidirectional"))
      (node (ref "NAPPE-LED2") (pin "K") (pinfunction "C_K") (pintype "bidirectional"))
    )
    (net (code "66") (name "Net-(NAPPE-LED2-PadA)") (class "Default")
      (node (ref "NAPPE-LED2") (pin "A") (pinfunction "A_A") (pintype "bidirectional"))
      (node (ref "R47") (pin "2") (pinfunction "2_2") (pintype "bidirectional"))
    )
    (net (code "67") (name "Net-(NAPPE-LED3-C)") (class "Default")
      (node (ref "NAPPE-LED3") (pin "K") (pinfunction "C_K") (pintype "bidirectional"))
      (node (ref "NAPPE-LED6") (pin "K") (pinfunction "C_K") (pintype "bidirectional"))
    )
    (net (code "68") (name "Net-(NAPPE-LED4-C)") (class "Default")
      (node (ref "NAPPE-LED3") (pin "A") (pinfunction "A_A") (pintype "bidirectional"))
      (node (ref "NAPPE-LED4") (pin "K") (pinfunction "C_K") (pintype "bidirectional"))
    )
    (net (code "69") (name "Net-(NAPPE-LED5-C)") (class "Default")
      (node (ref "NAPPE-LED4") (pin "A") (pinfunction "A_A") (pintype "bidirectional"))
      (node (ref "NAPPE-LED5") (pin "K") (pinfunction "C_K") (pintype "bidirectional"))
    )
    (net (code "70") (name "Net-(NAPPE-LED5-PadA)") (class "Default")
      (node (ref "NAPPE-LED5") (pin "A") (pinfunction "A_A") (pintype "bidirectional"))
      (node (ref "R49") (pin "2") (pinfunction "2_2") (pintype "bidirectional"))
    )
    (net (code "71") (name "Net-(NAPPE-LED7-C)") (class "Default")
      (node (ref "NAPPE-LED6") (pin "A") (pinfunction "A_A") (pintype "bidirectional"))
      (node (ref "NAPPE-LED7") (pin "K") (pinfunction "C_K") (pintype "bidirectional"))
    )
    (net (code "72") (name "Net-(NAPPE-LED8-C)") (class "Default")
      (node (ref "NAPPE-LED7") (pin "A") (pinfunction "A_A") (pintype "bidirectional"))
      (node (ref "NAPPE-LED8") (pin "K") (pinfunction "C_K") (pintype "bidirectional"))
    )
    (net (code "73") (name "Net-(NAPPE-LED8-PadA)") (class "Default")
      (node (ref "NAPPE-LED8") (pin "A") (pinfunction "A_A") (pintype "bidirectional"))
      (node (ref "R50") (pin "2") (pinfunction "2_2") (pintype "bidirectional"))
    )
    (net (code "74") (name "Net-(NAPPE-LED10-C)") (class "Default")
      (node (ref "NAPPE-LED10") (pin "K") (pinfunction "C_K") (pintype "bidirectional"))
      (node (ref "NAPPE-LED9") (pin "A") (pinfunction "A_A") (pintype "bidirectional"))
    )
    (net (code "75") (name "Net-(NAPPE-LED11-C)") (class "Default")
      (node (ref "NAPPE-LED10") (pin "A") (pinfunction "A_A") (pintype "bidirectional"))
      (node (ref "NAPPE-LED11") (pin "K") (pinfunction "C_K") (pintype "bidirectional"))
    )
    (net (code "76") (name "Net-(NAPPE-LED11-PadA)") (class "Default")
      (node (ref "NAPPE-LED11") (pin "A") (pinfunction "A_A") (pintype "bidirectional"))
      (node (ref "R51") (pin "2") (pinfunction "2_2") (pintype "bidirectional"))
    )
    (net (code "77") (name "Net-(NPN1-B)") (class "Default")
      (node (ref "NPN1") (pin "2") (pinfunction "B_2") (pintype "unspecified"))
      (node (ref "RA01") (pin "1") (pinfunction "1_1") (pintype "bidirectional"))
    )
    (net (code "78") (name "Net-(NPN1-C)") (class "Default")
      (node (ref "NPN1") (pin "3") (pinfunction "C_3") (pintype "unspecified"))
      (node (ref "U1") (pin "2") (pinfunction "2_2") (pintype "unspecified"))
    )
    (net (code "79") (name "Net-(NPN2-B)") (class "Default")
      (node (ref "NPN2") (pin "2") (pinfunction "B_2") (pintype "unspecified"))
      (node (ref "RA02") (pin "1") (pinfunction "1_1") (pintype "bidirectional"))
    )
    (net (code "80") (name "Net-(NPN2-C)") (class "Default")
      (node (ref "LED3") (pin "2") (pinfunction "2_2") (pintype "unspecified"))
      (node (ref "NPN2") (pin "3") (pinfunction "C_3") (pintype "unspecified"))
      (node (ref "U2") (pin "2") (pinfunction "2_2") (pintype "unspecified"))
    )
    (net (code "81") (name "Net-(R47-Pad1)") (class "Default")
      (node (ref "R47") (pin "1") (pinfunction "1_1") (pintype "bidirectional"))
      (node (ref "R49") (pin "1") (pinfunction "1_1") (pintype "bidirectional"))
      (node (ref "R50") (pin "1") (pinfunction "1_1") (pintype "bidirectional"))
    )
    (net (code "82") (name "Net-(RH01-Pad2)") (class "Default")
      (node (ref "RH01") (pin "2") (pinfunction "2_2") (pintype "input"))
      (node (ref "RH7") (pin "2") (pinfunction "2_2") (pintype "unspecified"))
    )
    (net (code "83") (name "Net-(RH02-Pad2)") (class "Default")
      (node (ref "RH02") (pin "2") (pinfunction "2_2") (pintype "input"))
      (node (ref "RH8") (pin "2") (pinfunction "2_2") (pintype "unspecified"))
    )
    (net (code "84") (name "Net-(RH03-Pad2)") (class "Default")
      (node (ref "RH03") (pin "2") (pinfunction "2_2") (pintype "input"))
      (node (ref "RH9") (pin "2") (pinfunction "2_2") (pintype "unspecified"))
    )
    (net (code "85") (name "Net-(RH04-Pad2)") (class "Default")
      (node (ref "RH04") (pin "2") (pinfunction "2_2") (pintype "input"))
      (node (ref "RH10") (pin "2") (pinfunction "2_2") (pintype "unspecified"))
    )
    (net (code "86") (name "Net-(RH05-Pad2)") (class "Default")
      (node (ref "RH05") (pin "2") (pinfunction "2_2") (pintype "input"))
      (node (ref "RH11") (pin "2") (pinfunction "2_2") (pintype "unspecified"))
    )
    (net (code "87") (name "Net-(RH06-Pad2)") (class "Default")
      (node (ref "RH06") (pin "2") (pinfunction "2_2") (pintype "input"))
      (node (ref "RH12") (pin "2") (pinfunction "2_2") (pintype "unspecified"))
    )
    (net (code "88") (name "Net-(SP1-2)") (class "Default")
      (node (ref "SP1") (pin "-") (pinfunction "2_-") (pintype "bidirectional"))
      (node (ref "SP2") (pin "+") (pinfunction "1_+") (pintype "bidirectional"))
    )
    (net (code "89") (name "Net-(U4-O1)") (class "Default")
      (node (ref "RELAY0-7") (pin "8") (pinfunction "8_8") (pintype "unspecified"))
      (node (ref "U4") (pin "18") (pinfunction "O1_18") (pintype "unspecified"))
    )
    (net (code "90") (name "Net-(U4-O2)") (class "Default")
      (node (ref "RELAY0-7") (pin "7") (pinfunction "7_7") (pintype "unspecified"))
      (node (ref "U4") (pin "17") (pinfunction "O2_17") (pintype "unspecified"))
    )
    (net (code "91") (name "Net-(U4-O3)") (class "Default")
      (node (ref "RELAY0-7") (pin "6") (pinfunction "6_6") (pintype "unspecified"))
      (node (ref "U4") (pin "16") (pinfunction "O3_16") (pintype "unspecified"))
    )
    (net (code "92") (name "Net-(U4-O4)") (class "Default")
      (node (ref "RELAY0-7") (pin "5") (pinfunction "5_5") (pintype "unspecified"))
      (node (ref "U4") (pin "15") (pinfunction "O4_15") (pintype "unspecified"))
    )
    (net (code "93") (name "Net-(U4-O5)") (class "Default")
      (node (ref "RELAY0-7") (pin "4") (pinfunction "4_4") (pintype "unspecified"))
      (node (ref "U4") (pin "14") (pinfunction "O5_14") (pintype "unspecified"))
    )
    (net (code "94") (name "Net-(U4-O6)") (class "Default")
      (node (ref "RELAY0-7") (pin "3") (pinfunction "3_3") (pintype "unspecified"))
      (node (ref "U4") (pin "13") (pinfunction "O6_13") (pintype "unspecified"))
    )
    (net (code "95") (name "Net-(U4-O7)") (class "Default")
      (node (ref "RELAY0-7") (pin "2") (pinfunction "2_2") (pintype "unspecified"))
      (node (ref "U4") (pin "12") (pinfunction "O7_12") (pintype "unspecified"))
    )
    (net (code "96") (name "Net-(U4-O8)") (class "Default")
      (node (ref "RELAY0-7") (pin "1") (pinfunction "1_1") (pintype "unspecified"))
      (node (ref "U4") (pin "11") (pinfunction "O8_11") (pintype "unspecified"))
    )
    (net (code "97") (name "Net-(U5-O1)") (class "Default")
      (node (ref "RELAY8-15") (pin "8") (pinfunction "8_8") (pintype "unspecified"))
      (node (ref "U5") (pin "18") (pinfunction "O1_18") (pintype "unspecified"))
    )
    (net (code "98") (name "Net-(U5-O2)") (class "Default")
      (node (ref "RELAY8-15") (pin "7") (pinfunction "7_7") (pintype "unspecified"))
      (node (ref "U5") (pin "17") (pinfunction "O2_17") (pintype "unspecified"))
    )
    (net (code "99") (name "Net-(U5-O3)") (class "Default")
      (node (ref "RELAY8-15") (pin "6") (pinfunction "6_6") (pintype "unspecified"))
      (node (ref "U5") (pin "16") (pinfunction "O3_16") (pintype "unspecified"))
    )
    (net (code "100") (name "Net-(U5-O4)") (class "Default")
      (node (ref "RELAY8-15") (pin "5") (pinfunction "5_5") (pintype "unspecified"))
      (node (ref "U5") (pin "15") (pinfunction "O4_15") (pintype "unspecified"))
    )
    (net (code "101") (name "Net-(U5-O5)") (class "Default")
      (node (ref "RELAY8-15") (pin "4") (pinfunction "4_4") (pintype "unspecified"))
      (node (ref "U5") (pin "14") (pinfunction "O5_14") (pintype "unspecified"))
    )
    (net (code "102") (name "Net-(U5-O6)") (class "Default")
      (node (ref "RELAY8-15") (pin "3") (pinfunction "3_3") (pintype "unspecified"))
      (node (ref "U5") (pin "13") (pinfunction "O6_13") (pintype "unspecified"))
    )
    (net (code "103") (name "Net-(U5-O7)") (class "Default")
      (node (ref "RELAY8-15") (pin "2") (pinfunction "2_2") (pintype "unspecified"))
      (node (ref "U5") (pin "12") (pinfunction "O7_12") (pintype "unspecified"))
    )
    (net (code "104") (name "Net-(U5-O8)") (class "Default")
      (node (ref "RELAY8-15") (pin "1") (pinfunction "1_1") (pintype "unspecified"))
      (node (ref "U5") (pin "11") (pinfunction "O8_11") (pintype "unspecified"))
    )
    (net (code "105") (name "Net-(U6-3V3)") (class "Default")
      (node (ref "J5") (pin "14") (pinfunction "14_14") (pintype "unspecified"))
      (node (ref "U6") (pin "17") (pinfunction "3V3_17") (pintype "unspecified"))
    )
    (net (code "106") (name "Net-(U6-A0)") (class "Default")
      (node (ref "J5") (pin "12") (pinfunction "12_12") (pintype "unspecified"))
      (node (ref "U6") (pin "19") (pinfunction "A0_19") (pintype "unspecified"))
    )
    (net (code "107") (name "Net-(U6-A1)") (class "Default")
      (node (ref "J5") (pin "11") (pinfunction "11_11") (pintype "unspecified"))
      (node (ref "U6") (pin "20") (pinfunction "A1_20") (pintype "unspecified"))
    )
    (net (code "108") (name "Net-(U6-A2)") (class "Default")
      (node (ref "J5") (pin "10") (pinfunction "10_10") (pintype "unspecified"))
      (node (ref "U6") (pin "21") (pinfunction "A2_21") (pintype "unspecified"))
    )
    (net (code "109") (name "Net-(U6-A3)") (class "Default")
      (node (ref "J0") (pin "2") (pinfunction "2_2") (pintype "unspecified"))
      (node (ref "J1") (pin "2") (pinfunction "2_2") (pintype "unspecified"))
      (node (ref "J2") (pin "2") (pinfunction "2_2") (pintype "unspecified"))
      (node (ref "J3") (pin "2") (pinfunction "2_2") (pintype "unspecified"))
      (node (ref "J4") (pin "2") (pinfunction "2_2") (pintype "unspecified"))
      (node (ref "J5") (pin "9") (pinfunction "9_9") (pintype "unspecified"))
      (node (ref "R000") (pin "2") (pinfunction "2_2") (pintype "bidirectional"))
      (node (ref "U6") (pin "22") (pinfunction "A3_22") (pintype "unspecified"))
    )
    (net (code "110") (name "Net-(U6-A6)") (class "Default")
      (node (ref "J5") (pin "6") (pinfunction "6_6") (pintype "unspecified"))
      (node (ref "U6") (pin "25") (pinfunction "A6_25") (pintype "unspecified"))
    )
    (net (code "111") (name "Net-(U6-A7)") (class "Default")
      (node (ref "J5") (pin "5") (pinfunction "5_5") (pintype "unspecified"))
      (node (ref "U6") (pin "26") (pinfunction "A7_26") (pintype "unspecified"))
    )
    (net (code "112") (name "Net-(U6-AREF)") (class "Default")
      (node (ref "J5") (pin "13") (pinfunction "13_13") (pintype "unspecified"))
      (node (ref "U6") (pin "18") (pinfunction "AREF_18") (pintype "unspecified"))
    )
    (net (code "113") (name "Net-(U6-D0{slash}RX)") (class "Default")
      (node (ref "J7") (pin "2") (pinfunction "2_2") (pintype "unspecified"))
      (node (ref "U6") (pin "2") (pinfunction "D0/RX_2") (pintype "unspecified"))
    )
    (net (code "114") (name "Net-(U6-D1{slash}TX)") (class "Default")
      (node (ref "J7") (pin "1") (pinfunction "1_1") (pintype "unspecified"))
      (node (ref "U6") (pin "1") (pinfunction "D1/TX_1") (pintype "unspecified"))
    )
    (net (code "115") (name "Net-(U6-D2)") (class "Default")
      (node (ref "J7") (pin "5") (pinfunction "5_5") (pintype "unspecified"))
      (node (ref "U6") (pin "5") (pinfunction "D2_5") (pintype "unspecified"))
    )
    (net (code "116") (name "Net-(U6-D3)") (class "Default")
      (node (ref "J7") (pin "6") (pinfunction "6_6") (pintype "unspecified"))
      (node (ref "U6") (pin "6") (pinfunction "D3_6") (pintype "unspecified"))
    )
    (net (code "117") (name "Net-(U6-D4)") (class "Default")
      (node (ref "J7") (pin "7") (pinfunction "7_7") (pintype "unspecified"))
      (node (ref "U6") (pin "7") (pinfunction "D4_7") (pintype "unspecified"))
    )
    (net (code "118") (name "Net-(U6-D5)") (class "Default")
      (node (ref "J7") (pin "8") (pinfunction "8_8") (pintype "unspecified"))
      (node (ref "U6") (pin "8") (pinfunction "D5_8") (pintype "unspecified"))
    )
    (net (code "119") (name "Net-(U6-D6)") (class "Default")
      (node (ref "J7") (pin "9") (pinfunction "9_9") (pintype "unspecified"))
      (node (ref "U6") (pin "9") (pinfunction "D6_9") (pintype "unspecified"))
    )
    (net (code "120") (name "Net-(U6-D7)") (class "Default")
      (node (ref "J7") (pin "10") (pinfunction "10_10") (pintype "unspecified"))
      (node (ref "U6") (pin "10") (pinfunction "D7_10") (pintype "unspecified"))
    )
    (net (code "121") (name "Net-(U6-D8)") (class "Default")
      (node (ref "J7") (pin "11") (pinfunction "11_11") (pintype "unspecified"))
      (node (ref "U6") (pin "11") (pinfunction "D8_11") (pintype "unspecified"))
    )
    (net (code "122") (name "Net-(U6-D9)") (class "Default")
      (node (ref "J7") (pin "12") (pinfunction "12_12") (pintype "unspecified"))
      (node (ref "U6") (pin "12") (pinfunction "D9_12") (pintype "unspecified"))
    )
    (net (code "123") (name "Net-(U6-D10)") (class "Default")
      (node (ref "J7") (pin "13") (pinfunction "13_13") (pintype "unspecified"))
      (node (ref "RHP2") (pin "1") (pinfunction "1_1") (pintype "bidirectional"))
      (node (ref "U6") (pin "13") (pinfunction "D10_13") (pintype "unspecified"))
    )
    (net (code "124") (name "Net-(U6-D11)") (class "Default")
      (node (ref "J7") (pin "14") (pinfunction "14_14") (pintype "unspecified"))
      (node (ref "RHP1") (pin "2") (pinfunction "2_2") (pintype "bidirectional"))
      (node (ref "U6") (pin "14") (pinfunction "D11_14") (pintype "unspecified"))
    )
    (net (code "125") (name "Net-(U6-D13)") (class "Default")
      (node (ref "J5") (pin "15") (pinfunction "15_15") (pintype "unspecified"))
      (node (ref "U6") (pin "16") (pinfunction "D13_16") (pintype "unspecified"))
    )
    (net (code "126") (name "Net-(U6-VIN)") (class "Default")
      (node (ref "J5") (pin "1") (pinfunction "1_1") (pintype "unspecified"))
      (node (ref "U6") (pin "30") (pinfunction "VIN_30") (pintype "unspecified"))
    )
    (net (code "127") (name "unconnected-(AUDIO1-ADKEY1-Pad12)") (class "Default")
      (node (ref "AUDIO1") (pin "12") (pinfunction "ADKEY1_12") (pintype "unspecified+no_connect"))
    )
    (net (code "128") (name "unconnected-(AUDIO1-ADKEY2-Pad13)") (class "Default")
      (node (ref "AUDIO1") (pin "13") (pinfunction "ADKEY2_13") (pintype "unspecified+no_connect"))
    )
    (net (code "129") (name "unconnected-(AUDIO1-DAC_L-Pad5)") (class "Default")
      (node (ref "AUDIO1") (pin "5") (pinfunction "DAC_L_5") (pintype "unspecified+no_connect"))
    )
    (net (code "130") (name "unconnected-(AUDIO1-DAC_R-Pad4)") (class "Default")
      (node (ref "AUDIO1") (pin "4") (pinfunction "DAC_R_4") (pintype "unspecified+no_connect"))
    )
    (net (code "131") (name "unconnected-(AUDIO1-IO_1-Pad9)") (class "Default")
      (node (ref "AUDIO1") (pin "9") (pinfunction "IO_1_9") (pintype "unspecified+no_connect"))
    )
    (net (code "132") (name "unconnected-(AUDIO1-IO_2-Pad11)") (class "Default")
      (node (ref "AUDIO1") (pin "11") (pinfunction "IO_2_11") (pintype "unspecified+no_connect"))
    )
    (net (code "133") (name "unconnected-(AUDIO1-USB+-Pad14)") (class "Default")
      (node (ref "AUDIO1") (pin "14") (pinfunction "USB+_14") (pintype "unspecified+no_connect"))
    )
    (net (code "134") (name "unconnected-(AUDIO1-USB--Pad15)") (class "Default")
      (node (ref "AUDIO1") (pin "15") (pinfunction "USB-_15") (pintype "unspecified+no_connect"))
    )
    (net (code "135") (name "unconnected-(MCP0-GPB6-Pad7)") (class "Default")
      (node (ref "MCP0") (pin "7") (pinfunction "GPB6_7") (pintype "unspecified+no_connect"))
    )
    (net (code "136") (name "unconnected-(MCP0-GPB7-Pad8)") (class "Default")
      (node (ref "MCP0") (pin "8") (pinfunction "GPB7_8") (pintype "unspecified+no_connect"))
    )
    (net (code "137") (name "unconnected-(MCP0-INTA-Pad20)") (class "Default")
      (node (ref "MCP0") (pin "20") (pinfunction "INTA_20") (pintype "unspecified+no_connect"))
    )
    (net (code "138") (name "unconnected-(MCP0-INTB-Pad19)") (class "Default")
      (node (ref "MCP0") (pin "19") (pinfunction "INTB_19") (pintype "unspecified+no_connect"))
    )
    (net (code "139") (name "unconnected-(MCP0-NC-Pad11)") (class "Default")
      (node (ref "MCP0") (pin "11") (pinfunction "NC_11") (pintype "unspecified+no_connect"))
    )
    (net (code "140") (name "unconnected-(MCP0-NC-Pad14)") (class "Default")
      (node (ref "MCP0") (pin "14") (pinfunction "NC_14") (pintype "unspecified+no_connect"))
    )
    (net (code "141") (name "unconnected-(MCP1-INTA-Pad20)") (class "Default")
      (node (ref "MCP1") (pin "20") (pinfunction "INTA_20") (pintype "unspecified+no_connect"))
    )
    (net (code "142") (name "unconnected-(MCP1-INTB-Pad19)") (class "Default")
      (node (ref "MCP1") (pin "19") (pinfunction "INTB_19") (pintype "unspecified+no_connect"))
    )
    (net (code "143") (name "unconnected-(MCP1-NC-Pad11)") (class "Default")
      (node (ref "MCP1") (pin "11") (pinfunction "NC_11") (pintype "unspecified+no_connect"))
    )
    (net (code "144") (name "unconnected-(MCP1-NC-Pad14)") (class "Default")
      (node (ref "MCP1") (pin "14") (pinfunction "NC_14") (pintype "unspecified+no_connect"))
    )
    (net (code "145") (name "unconnected-(NAPPE-LED9-C-PadK)") (class "Default")
      (node (ref "NAPPE-LED9") (pin "K") (pinfunction "C_K") (pintype "bidirectional+no_connect"))
    )
    (net (code "146") (name "unconnected-(NAPPE-LED13-C-PadK)") (class "Default")
      (node (ref "NAPPE-LED13") (pin "K") (pinfunction "C_K") (pintype "bidirectional+no_connect"))
    )
    (net (code "147") (name "unconnected-(R51-Pad1)") (class "Default")
      (node (ref "R51") (pin "1") (pinfunction "1_1") (pintype "bidirectional+no_connect"))
    )
    (net (code "148") (name "unconnected-(RH01-Pad1)") (class "Default")
      (node (ref "RH01") (pin "1") (pinfunction "1_1") (pintype "input"))
    )
    (net (code "149") (name "unconnected-(RH02-Pad1)") (class "Default")
      (node (ref "RH02") (pin "1") (pinfunction "1_1") (pintype "input"))
    )
    (net (code "150") (name "unconnected-(RH03-Pad1)") (class "Default")
      (node (ref "RH03") (pin "1") (pinfunction "1_1") (pintype "input"))
    )
    (net (code "151") (name "unconnected-(RH04-Pad1)") (class "Default")
      (node (ref "RH04") (pin "1") (pinfunction "1_1") (pintype "input"))
    )
    (net (code "152") (name "unconnected-(RH05-Pad1)") (class "Default")
      (node (ref "RH05") (pin "1") (pinfunction "1_1") (pintype "input"))
    )
    (net (code "153") (name "unconnected-(RH06-Pad1)") (class "Default")
      (node (ref "RH06") (pin "1") (pinfunction "1_1") (pintype "input"))
    )
    (net (code "154") (name "unconnected-(SP1-1-Pad+)") (class "Default")
      (node (ref "SP1") (pin "+") (pinfunction "1_+") (pintype "bidirectional+no_connect"))
    )
    (net (code "155") (name "unconnected-(SP2-2-Pad-)") (class "Default")
      (node (ref "SP2") (pin "-") (pinfunction "2_-") (pintype "bidirectional+no_connect"))
    )
  )
)
